# clock-kit-board.net
KiCad netlist of a schematic drawn in EAGLE
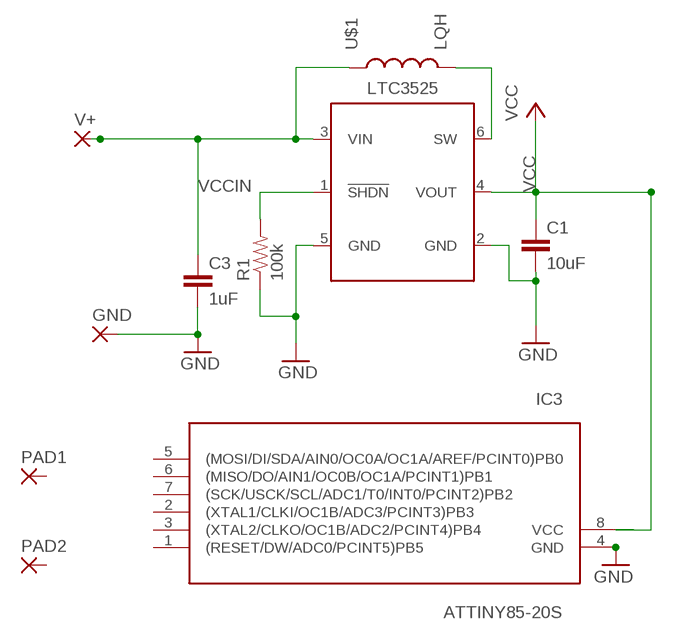
[diagram p0: schematic, sheet 1]

(export (version "E")
  (design (tool "Eeschema 10.0.6"))
  (components
    (comp (ref "C1")
      (value "10uF")
      (footprint "eagle-import:0805")
      (libsource (lib "eagle-import") (part "CAP0805"))
    )
    (comp (ref "C3")
      (value "1uF")
      (footprint "eagle-import:0805")
      (libsource (lib "eagle-import") (part "CAP0805"))
    )
    (comp (ref "GND")
      (value "SMD5")
      (footprint "eagle-import:SMD2,54-5,08")
      (libsource (lib "eagle-import") (part "SMD5"))
    )
    (comp (ref "IC3")
      (value "ATTINY85-20S")
      (footprint "eagle-import:SOIC8")
      (libsource (lib "eagle-import") (part "ATTINY85SV-10"))
    )
    (comp (ref "PAD1")
      (value "2,54/1,1")
      (footprint "eagle-import:2,54_1,1")
      (libsource (lib "eagle-import") (part "2,54/1,1"))
    )
    (comp (ref "PAD2")
      (value "2,54/1,1")
      (footprint "eagle-import:2,54_1,1")
      (libsource (lib "eagle-import") (part "2,54/1,1"))
    )
    (comp (ref "R1")
      (value "100k")
      (footprint "eagle-import:0805")
      (libsource (lib "eagle-import") (part "RESISTOR0805-RES"))
    )
    (comp (ref "U$1")
      (value "LQH")
      (footprint "eagle-import:LQH32")
      (libsource (lib "eagle-import") (part "LQH"))
    )
    (comp (ref "U$3")
      (value "LTC3525")
      (footprint "eagle-import:SC70-6L")
      (libsource (lib "eagle-import") (part "LTC3525"))
    )
    (comp (ref "V+")
      (value "SMD5")
      (footprint "eagle-import:SMD2,54-5,08")
      (libsource (lib "eagle-import") (part "SMD5"))
    )
  )
  (nets
    (net (code "1") (name "/VCCIN") (class "Default")
      (node (ref "C3") (pin "1") (pinfunction "1_1") (pintype "passive"))
      (node (ref "U$1") (pin "1") (pinfunction "1_1") (pintype "passive"))
      (node (ref "U$3") (pin "3") (pinfunction "VIN_3") (pintype "input"))
      (node (ref "V+") (pin "1") (pinfunction "P_1") (pintype "passive"))
    )
    (net (code "2") (name "GND") (class "Default")
      (node (ref "C1") (pin "2") (pinfunction "2_2") (pintype "passive"))
      (node (ref "C3") (pin "2") (pinfunction "2_2") (pintype "passive"))
      (node (ref "GND") (pin "1") (pinfunction "P_1") (pintype "passive"))
      (node (ref "IC3") (pin "4") (pinfunction "GND_4") (pintype "bidirectional"))
      (node (ref "R1") (pin "1") (pinfunction "1_1") (pintype "passive"))
      (node (ref "U$3") (pin "2") (pinfunction "GND_2") (pintype "power_in"))
      (node (ref "U$3") (pin "5") (pinfunction "GND_5") (pintype "input"))
    )
    (net (code "3") (name "Net-(U$3-SW)") (class "Default")
      (node (ref "U$1") (pin "2") (pinfunction "2_2") (pintype "passive"))
      (node (ref "U$3") (pin "6") (pinfunction "SW_6") (pintype "passive"))
    )
    (net (code "4") (name "Net-(U$3-~{SHDN})") (class "Default")
      (node (ref "R1") (pin "2") (pinfunction "2_2") (pintype "passive"))
      (node (ref "U$3") (pin "1") (pinfunction "~{SHDN}_1") (pintype "passive"))
    )
    (net (code "5") (name "VCC") (class "Default")
      (node (ref "C1") (pin "1") (pinfunction "1_1") (pintype "passive"))
      (node (ref "IC3") (pin "8") (pinfunction "VCC_8") (pintype "bidirectional"))
      (node (ref "U$3") (pin "4") (pinfunction "VOUT_4") (pintype "passive"))
    )
    (net (code "6") (name "unconnected-(IC3-(MISO{slash}DO{slash}AIN1{slash}OC0B{slash}OC1A{slash}PCINT1)PB1-Pad6)") (class "Default")
      (node (ref "IC3") (pin "6") (pinfunction "(MISO/DO/AIN1/OC0B/OC1A/PCINT1)PB1_6") (pintype "bidirectional"))
    )
    (net (code "7") (name "unconnected-(IC3-(MOSI{slash}DI{slash}SDA{slash}AIN0{slash}OC0A{slash}OC1A{slash}AREF{slash}PCINT0)PB0-Pad5)") (class "Default")
      (node (ref "IC3") (pin "5") (pinfunction "(MOSI/DI/SDA/AIN0/OC0A/OC1A/AREF/PCINT0)PB0_5") (pintype "bidirectional"))
    )
    (net (code "8") (name "unconnected-(IC3-(RESET{slash}DW{slash}ADC0{slash}PCINT5)PB5-Pad1)") (class "Default")
      (node (ref "IC3") (pin "1") (pinfunction "(RESET/DW/ADC0/PCINT5)PB5_1") (pintype "bidirectional"))
    )
    (net (code "9") (name "unconnected-(IC3-(SCK{slash}USCK{slash}SCL{slash}ADC1{slash}T0{slash}INT0{slash}PCINT2)PB2-Pad7)") (class "Default")
      (node (ref "IC3") (pin "7") (pinfunction "(SCK/USCK/SCL/ADC1/T0/INT0/PCINT2)PB2_7") (pintype "bidirectional"))
    )
    (net (code "10") (name "unconnected-(IC3-(XTAL1{slash}CLKI{slash}OC1B{slash}ADC3{slash}PCINT3)PB3-Pad2)") (class "Default")
      (node (ref "IC3") (pin "2") (pinfunction "(XTAL1/CLKI/OC1B/ADC3/PCINT3)PB3_2") (pintype "bidirectional"))
    )
    (net (code "11") (name "unconnected-(IC3-(XTAL2{slash}CLKO{slash}OC1B{slash}ADC2{slash}PCINT4)PB4-Pad3)") (class "Default")
      (node (ref "IC3") (pin "3") (pinfunction "(XTAL2/CLKO/OC1B/ADC2/PCINT4)PB4_3") (pintype "bidirectional"))
    )
    (net (code "12") (name "unconnected-(PAD1-P-Pad1)") (class "Default")
      (node (ref "PAD1") (pin "1") (pinfunction "P_1") (pintype "passive"))
    )
    (net (code "13") (name "unconnected-(PAD2-P-Pad1)") (class "Default")
      (node (ref "PAD2") (pin "1") (pinfunction "P_1") (pintype "passive"))
    )
  )
)
